# MBP-Wireless-Upgrade.net
KiCad netlist of a schematic drawn in Altium Designer
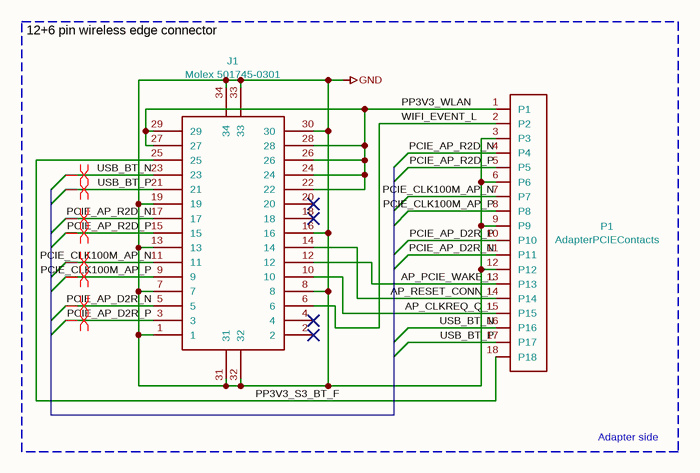
[diagram p0: MBP-Wireless-Upgrade.SchDoc]

(export (version "E")
  (design (tool "Eeschema 10.0.6"))
  (components
    (comp (ref "J1")
      (value "Molex 501745-0301")
      (footprint "5017450301")
      (fields
        (field (name "MOUSER PART NUMBER") "538-501745-0301")
        (field (name "MANUFACTURER_PART_NUMBER") "501745-0301")
      )
      (libsource (lib "SamacSys_Parts") (part "501745-0301"))
    )
    (comp (ref "P1")
      (value "AdapterPCIEContacts")
      (footprint "Edge Connector")
      (libsource (lib "MBPWirelessParts") (part "AdapterPCIEContacts"))
    )
  )
  (nets
    (net (code "1") (name "/AP_CLKREQ_Q_L") (class "Default")
      (node (ref "J1") (pin "10") (pinfunction "10_10") (pintype "passive"))
      (node (ref "P1") (pin "15") (pinfunction "P15_15") (pintype "passive"))
    )
    (net (code "2") (name "/AP_PCIE_WAKE_L") (class "Default")
      (node (ref "J1") (pin "12") (pinfunction "12_12") (pintype "passive"))
      (node (ref "P1") (pin "13") (pinfunction "P13_13") (pintype "passive"))
    )
    (net (code "3") (name "/AP_RESET_CONN_L") (class "Default")
      (node (ref "J1") (pin "14") (pinfunction "14_14") (pintype "passive"))
      (node (ref "P1") (pin "14") (pinfunction "P14_14") (pintype "passive"))
    )
    (net (code "4") (name "/PCIE_AP_D2R_N") (class "Default")
      (node (ref "J1") (pin "5") (pinfunction "5_5") (pintype "passive"))
      (node (ref "P1") (pin "11") (pinfunction "P11_11") (pintype "passive"))
    )
    (net (code "5") (name "/PCIE_AP_D2R_P") (class "Default")
      (node (ref "J1") (pin "3") (pinfunction "3_3") (pintype "passive"))
      (node (ref "P1") (pin "10") (pinfunction "P10_10") (pintype "passive"))
    )
    (net (code "6") (name "/PCIE_AP_R2D_N") (class "Default")
      (node (ref "J1") (pin "17") (pinfunction "17_17") (pintype "passive"))
      (node (ref "P1") (pin "4") (pinfunction "P4_4") (pintype "passive"))
    )
    (net (code "7") (name "/PCIE_AP_R2D_P") (class "Default")
      (node (ref "J1") (pin "15") (pinfunction "15_15") (pintype "passive"))
      (node (ref "P1") (pin "5") (pinfunction "P5_5") (pintype "passive"))
    )
    (net (code "8") (name "/PCIE_CLK100M_AP_N") (class "Default")
      (node (ref "J1") (pin "11") (pinfunction "11_11") (pintype "passive"))
      (node (ref "P1") (pin "7") (pinfunction "P7_7") (pintype "passive"))
    )
    (net (code "9") (name "/PCIE_CLK100M_AP_P") (class "Default")
      (node (ref "J1") (pin "9") (pinfunction "9_9") (pintype "passive"))
      (node (ref "P1") (pin "8") (pinfunction "P8_8") (pintype "passive"))
    )
    (net (code "10") (name "/PP3V3_S3_BT_F") (class "Default")
      (node (ref "J1") (pin "25") (pinfunction "25_25") (pintype "passive"))
      (node (ref "P1") (pin "18") (pinfunction "P18_18") (pintype "passive"))
    )
    (net (code "11") (name "/PP3V3_WLAN") (class "Default")
      (node (ref "J1") (pin "22") (pinfunction "22_22") (pintype "passive"))
      (node (ref "J1") (pin "24") (pinfunction "24_24") (pintype "passive"))
      (node (ref "J1") (pin "26") (pinfunction "26_26") (pintype "passive"))
      (node (ref "J1") (pin "27") (pinfunction "27_27") (pintype "passive"))
      (node (ref "J1") (pin "28") (pinfunction "28_28") (pintype "passive"))
      (node (ref "J1") (pin "29") (pinfunction "29_29") (pintype "passive"))
      (node (ref "P1") (pin "1") (pinfunction "P1_1") (pintype "passive"))
    )
    (net (code "12") (name "/USB_BT_N") (class "Default")
      (node (ref "J1") (pin "23") (pinfunction "23_23") (pintype "passive"))
      (node (ref "P1") (pin "16") (pinfunction "P16_16") (pintype "passive"))
    )
    (net (code "13") (name "/USB_BT_P") (class "Default")
      (node (ref "J1") (pin "21") (pinfunction "21_21") (pintype "passive"))
      (node (ref "P1") (pin "17") (pinfunction "P17_17") (pintype "passive"))
    )
    (net (code "14") (name "/WIFI_EVENT_L") (class "Default")
      (node (ref "J1") (pin "6") (pinfunction "6_6") (pintype "passive"))
      (node (ref "P1") (pin "2") (pinfunction "P2_2") (pintype "passive"))
    )
    (net (code "15") (name "GND") (class "Default")
      (node (ref "J1") (pin "1") (pinfunction "1_1") (pintype "passive"))
      (node (ref "J1") (pin "13") (pinfunction "13_13") (pintype "passive"))
      (node (ref "J1") (pin "16") (pinfunction "16_16") (pintype "passive"))
      (node (ref "J1") (pin "19") (pinfunction "19_19") (pintype "passive"))
      (node (ref "J1") (pin "30") (pinfunction "30_30") (pintype "passive"))
      (node (ref "J1") (pin "31") (pinfunction "31_31") (pintype "passive"))
      (node (ref "J1") (pin "32") (pinfunction "32_32") (pintype "passive"))
      (node (ref "J1") (pin "33") (pinfunction "33_33") (pintype "passive"))
      (node (ref "J1") (pin "34") (pinfunction "34_34") (pintype "passive"))
      (node (ref "J1") (pin "7") (pinfunction "7_7") (pintype "passive"))
      (node (ref "J1") (pin "8") (pinfunction "8_8") (pintype "passive"))
      (node (ref "P1") (pin "12") (pinfunction "P12_12") (pintype "passive"))
      (node (ref "P1") (pin "3") (pinfunction "P3_3") (pintype "passive"))
      (node (ref "P1") (pin "6") (pinfunction "P6_6") (pintype "passive"))
      (node (ref "P1") (pin "9") (pinfunction "P9_9") (pintype "passive"))
    )
    (net (code "16") (name "unconnected-(J1-Pad2)") (class "Default")
      (node (ref "J1") (pin "2") (pinfunction "2_2") (pintype "passive+no_connect"))
    )
    (net (code "17") (name "unconnected-(J1-Pad4)") (class "Default")
      (node (ref "J1") (pin "4") (pinfunction "4_4") (pintype "passive+no_connect"))
    )
    (net (code "18") (name "unconnected-(J1-Pad18)") (class "Default")
      (node (ref "J1") (pin "18") (pinfunction "18_18") (pintype "passive+no_connect"))
    )
    (net (code "19") (name "unconnected-(J1-Pad20)") (class "Default")
      (node (ref "J1") (pin "20") (pinfunction "20_20") (pintype "passive+no_connect"))
    )
  )
)
